# 06-ETHERNET.net
KiCad netlist of a schematic drawn in Altium Designer
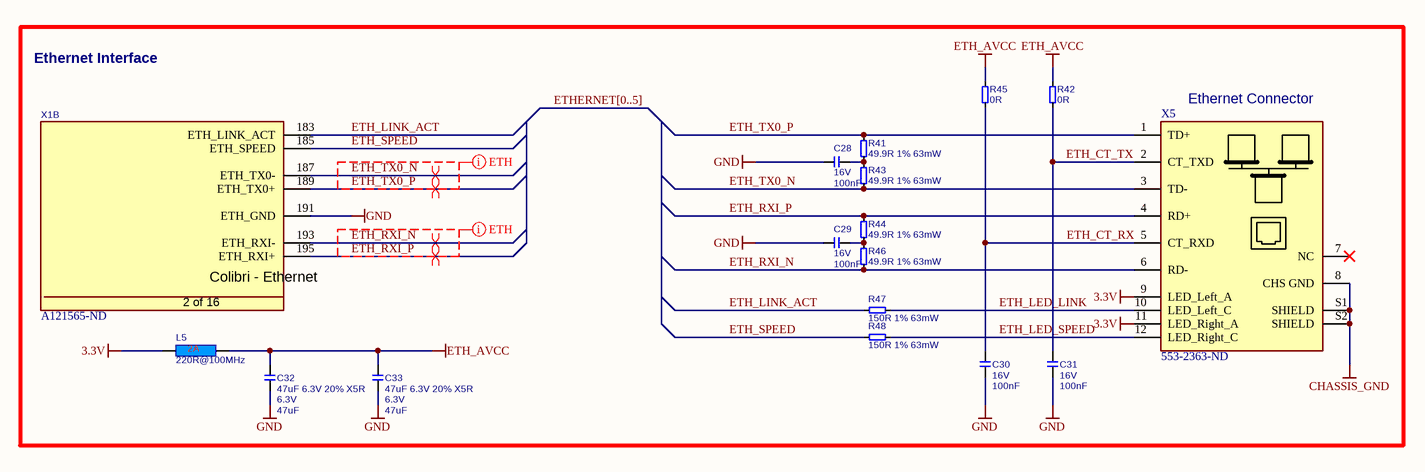
[diagram p0: 06-ETHERNET.SchDoc]

(export (version "E")
  (design (tool "Eeschema 10.0.6"))
  (components
    (comp (ref "C28")
      (value "100nF")
      (footprint "CAPC1005X60N")
      (description "Capacitor Ceramic X7R 100nF 16V 10% 0603")
      (fields
        (field (name "TOLERANCE") "10%")
        (field (name "RATING") "16V")
        (field (name "Comment") "100nF 16V 10% X7R")
      )
      (libsource (lib "AI Gateway - Carrier") (part "C-100nF-16V-10%-0603"))
    )
    (comp (ref "C29")
      (value "100nF")
      (footprint "CAPC1005X60N")
      (description "Capacitor Ceramic X7R 100nF 16V 10% 0603")
      (fields
        (field (name "TOLERANCE") "10%")
        (field (name "RATING") "16V")
        (field (name "Comment") "100nF 16V 10% X7R")
      )
      (libsource (lib "AI Gateway - Carrier") (part "C-100nF-16V-10%-0603"))
    )
    (comp (ref "C30")
      (value "100nF")
      (footprint "CAPC1005X60N")
      (description "Capacitor Ceramic X7R 100nF 16V 10% 0603")
      (fields
        (field (name "TOLERANCE") "10%")
        (field (name "RATING") "16V")
        (field (name "Comment") "100nF 16V 10% X7R")
      )
      (libsource (lib "AI Gateway - Carrier") (part "C-100nF-16V-10%-0603"))
    )
    (comp (ref "C31")
      (value "100nF")
      (footprint "CAPC1005X60N")
      (description "Capacitor Ceramic X7R 100nF 16V 10% 0603")
      (fields
        (field (name "TOLERANCE") "10%")
        (field (name "RATING") "16V")
        (field (name "Comment") "100nF 16V 10% X7R")
      )
      (libsource (lib "AI Gateway - Carrier") (part "C-100nF-16V-10%-0603"))
    )
    (comp (ref "C32")
      (value "47uF 6.3V 20% X5R")
      (footprint "T_CAPC0603X33N")
      (description "Capacitor Ceramic X5R 47uF 6.3V 20% 0603")
      (fields
        (field (name "TOLERANCE") "20%")
        (field (name "RATING") "6.3V")
        (field (name "ALTIUM_VALUE") "47uF")
      )
      (libsource (lib "AI Gateway - Carrier") (part "C-47uF-6.3V-20%-0603"))
    )
    (comp (ref "C33")
      (value "47uF 6.3V 20% X5R")
      (footprint "T_CAPC0603X33N")
      (description "Capacitor Ceramic X5R 47uF 6.3V 20% 0603")
      (fields
        (field (name "TOLERANCE") "20%")
        (field (name "RATING") "6.3V")
        (field (name "ALTIUM_VALUE") "47uF")
      )
      (libsource (lib "AI Gateway - Carrier") (part "C-47uF-6.3V-20%-0603"))
    )
    (comp (ref "L5")
      (value "220R@100MHz")
      (footprint "INDC2012X140N")
      (description "220 Ohms @ 100MHz 1 Power Line Ferrite Bead 0805 (2012 Metric) 2A 45mOhm")
      (fields (field (name "TOLERANCE") "25%") (field (name "MFG") "EXC-ML20A390U"))
      (libsource (lib "Passive") (part "L-Murata-220R@100MHz-2A-0805"))
    )
    (comp (ref "R41")
      (value "49.9R 1% 63mW")
      (footprint "RESC1005X40N")
      (description "Resistor 49.9ohm 63mW 1% 0402")
      (fields (field (name "POWER") "63mW") (field (name "TOLERANCE") "1%"))
      (libsource (lib "AI Gateway - Carrier") (part "R-49.9R-1%-0402"))
    )
    (comp (ref "R42")
      (value "0R")
      (footprint "RESC1005X40N")
      (description "Resistor 0ohm 0402")
      (fields (field (name "POWER") "?") (field (name "TOLERANCE") "1%"))
      (libsource (lib "AI Gateway - Carrier") (part "R-0R-0402"))
    )
    (comp (ref "R43")
      (value "49.9R 1% 63mW")
      (footprint "RESC1005X40N")
      (description "Resistor 49.9ohm 63mW 1% 0402")
      (fields (field (name "POWER") "63mW") (field (name "TOLERANCE") "1%"))
      (libsource (lib "AI Gateway - Carrier") (part "R-49.9R-1%-0402"))
    )
    (comp (ref "R44")
      (value "49.9R 1% 63mW")
      (footprint "RESC1005X40N")
      (description "Resistor 49.9ohm 63mW 1% 0402")
      (fields (field (name "POWER") "63mW") (field (name "TOLERANCE") "1%"))
      (libsource (lib "AI Gateway - Carrier") (part "R-49.9R-1%-0402"))
    )
    (comp (ref "R45")
      (value "0R")
      (footprint "RESC1005X40N")
      (description "Resistor 0ohm 0402")
      (fields (field (name "POWER") "?") (field (name "TOLERANCE") "1%"))
      (libsource (lib "AI Gateway - Carrier") (part "R-0R-0402"))
    )
    (comp (ref "R46")
      (value "49.9R 1% 63mW")
      (footprint "RESC1005X40N")
      (description "Resistor 49.9ohm 63mW 1% 0402")
      (fields (field (name "POWER") "63mW") (field (name "TOLERANCE") "1%"))
      (libsource (lib "AI Gateway - Carrier") (part "R-49.9R-1%-0402"))
    )
    (comp (ref "R47")
      (value "150R 1% 63mW")
      (footprint "RESC1005X40N")
      (description "Resistor 150ohm 63mW 1% 0402")
      (fields (field (name "POWER") "63mW") (field (name "TOLERANCE") "1%"))
      (libsource (lib "AI Gateway - Carrier") (part "R-150R-1%-0402"))
    )
    (comp (ref "R48")
      (value "150R 1% 63mW")
      (footprint "RESC1005X40N")
      (description "Resistor 150ohm 63mW 1% 0402")
      (fields (field (name "POWER") "63mW") (field (name "TOLERANCE") "1%"))
      (libsource (lib "AI Gateway - Carrier") (part "R-150R-1%-0402"))
    )
    (comp (ref "X1")
      (value "1473005-1")
      (footprint "T_Tyco_1473005-1")
      (description "SODIMM Connector")
      (fields (field (name "SUPPLIER PART NUMBER 1") "A121565-ND"))
      (libsource (lib "Connectors") (part "CON-Tyco-1473005-1-200-0.6mm"))
    )
    (comp (ref "X5")
      (value "JD2-0001NL")
      (footprint "T_PULSE_JD2-0001NL")
      (description "1 Port RJ45 Magjack Connector Through Hole 10/100 Base-TX, AutoMDIX")
      (fields
        (field (name "SUPPLIER PART NUMBER 1") "553-2363-ND")
        (field (name "MFG") "Pulse Electronics Network")
      )
      (libsource (lib "Connectors") (part "CON-Pulse-JD2-0001NL"))
    )
  )
  (nets
    (net (code "8") (name "/ETH_CT_RX") (class "Default")
      (node (ref "C30") (pin "2") (pinfunction "2_2") (pintype "passive"))
      (node (ref "R45") (pin "1") (pinfunction "1_1") (pintype "passive"))
      (node (ref "X5") (pin "5") (pinfunction "CT_RXD_5") (pintype "passive"))
    )
    (net (code "9") (name "/ETH_CT_TX") (class "Default")
      (node (ref "C31") (pin "2") (pinfunction "2_2") (pintype "passive"))
      (node (ref "R42") (pin "1") (pinfunction "1_1") (pintype "passive"))
      (node (ref "X5") (pin "2") (pinfunction "CT_TXD_2") (pintype "passive"))
    )
    (net (code "10") (name "/ETH_LED_LINK") (class "Default")
      (node (ref "R47") (pin "1") (pinfunction "1_1") (pintype "passive"))
      (node (ref "X5") (pin "10") (pinfunction "LED_Left_C_10") (pintype "passive"))
    )
    (net (code "11") (name "/ETH_LED_SPEED") (class "Default")
      (node (ref "R48") (pin "1") (pinfunction "1_1") (pintype "passive"))
      (node (ref "X5") (pin "12") (pinfunction "LED_Right_C_12") (pintype "passive"))
    )
    (net (code "12") (name "/ETH_LINK_ACT") (class "Default")
      (node (ref "R47") (pin "2") (pinfunction "2_2") (pintype "passive"))
      (node (ref "X1") (pin "183") (pinfunction "ETH_LINK_ACT_183") (pintype "passive"))
    )
    (net (code "13") (name "/ETH_RXI_N") (class "Default")
      (node (ref "R46") (pin "1") (pinfunction "1_1") (pintype "passive"))
      (node (ref "X1") (pin "193") (pinfunction "ETH_RXI-_193") (pintype "passive"))
      (node (ref "X5") (pin "6") (pinfunction "RD-_6") (pintype "passive"))
    )
    (net (code "14") (name "/ETH_RXI_P") (class "Default")
      (node (ref "R44") (pin "2") (pinfunction "2_2") (pintype "passive"))
      (node (ref "X1") (pin "195") (pinfunction "ETH_RXI+_195") (pintype "passive"))
      (node (ref "X5") (pin "4") (pinfunction "RD+_4") (pintype "passive"))
    )
    (net (code "15") (name "/ETH_SPEED") (class "Default")
      (node (ref "R48") (pin "2") (pinfunction "2_2") (pintype "passive"))
      (node (ref "X1") (pin "185") (pinfunction "ETH_SPEED_185") (pintype "passive"))
    )
    (net (code "16") (name "/ETH_TX0_N") (class "Default")
      (node (ref "R43") (pin "1") (pinfunction "1_1") (pintype "passive"))
      (node (ref "X1") (pin "187") (pinfunction "ETH_TX0-_187") (pintype "passive"))
      (node (ref "X5") (pin "3") (pinfunction "TD-_3") (pintype "passive"))
    )
    (net (code "17") (name "/ETH_TX0_P") (class "Default")
      (node (ref "R41") (pin "2") (pinfunction "2_2") (pintype "passive"))
      (node (ref "X1") (pin "189") (pinfunction "ETH_TX0+_189") (pintype "passive"))
      (node (ref "X5") (pin "1") (pinfunction "TD+_1") (pintype "passive"))
    )
    (net (code "18") (name "3.3V") (class "Default")
      (node (ref "L5") (pin "2") (pinfunction "2_2") (pintype "passive"))
      (node (ref "X5") (pin "11") (pinfunction "LED_Right_A_11") (pintype "passive"))
      (node (ref "X5") (pin "9") (pinfunction "LED_Left_A_9") (pintype "passive"))
    )
    (net (code "19") (name "CHASSIS_GND") (class "Default")
      (node (ref "X5") (pin "8") (pinfunction "CHS_GND_8") (pintype "passive"))
      (node (ref "X5") (pin "S1") (pinfunction "SHIELD_S1") (pintype "passive"))
      (node (ref "X5") (pin "S2") (pinfunction "SHIELD_S2") (pintype "passive"))
    )
    (net (code "20") (name "ETH_AVCC") (class "Default")
      (node (ref "C32") (pin "2") (pinfunction "2_2") (pintype "passive"))
      (node (ref "C33") (pin "2") (pinfunction "2_2") (pintype "passive"))
      (node (ref "L5") (pin "1") (pinfunction "1_1") (pintype "passive"))
      (node (ref "R42") (pin "2") (pinfunction "2_2") (pintype "passive"))
      (node (ref "R45") (pin "2") (pinfunction "2_2") (pintype "passive"))
    )
    (net (code "21") (name "GND") (class "Default")
      (node (ref "C28") (pin "2") (pinfunction "2_2") (pintype "passive"))
      (node (ref "C29") (pin "2") (pinfunction "2_2") (pintype "passive"))
      (node (ref "C30") (pin "1") (pinfunction "1_1") (pintype "passive"))
      (node (ref "C31") (pin "1") (pinfunction "1_1") (pintype "passive"))
      (node (ref "C32") (pin "1") (pinfunction "1_1") (pintype "passive"))
      (node (ref "C33") (pin "1") (pinfunction "1_1") (pintype "passive"))
      (node (ref "X1") (pin "191") (pinfunction "ETH_GND_191") (pintype "passive"))
    )
    (net (code "22") (name "Net-(C28-Pad1)") (class "Default")
      (node (ref "C28") (pin "1") (pinfunction "1_1") (pintype "passive"))
      (node (ref "R41") (pin "1") (pinfunction "1_1") (pintype "passive"))
      (node (ref "R43") (pin "2") (pinfunction "2_2") (pintype "passive"))
    )
    (net (code "23") (name "Net-(C29-Pad1)") (class "Default")
      (node (ref "C29") (pin "1") (pinfunction "1_1") (pintype "passive"))
      (node (ref "R44") (pin "1") (pinfunction "1_1") (pintype "passive"))
      (node (ref "R46") (pin "2") (pinfunction "2_2") (pintype "passive"))
    )
    (net (code "24") (name "unconnected-(X5-NC-Pad7)") (class "Default")
      (node (ref "X5") (pin "7") (pinfunction "NC_7") (pintype "passive+no_connect"))
    )
  )
)
